# timer.net
KiCad netlist of a schematic drawn in EAGLE
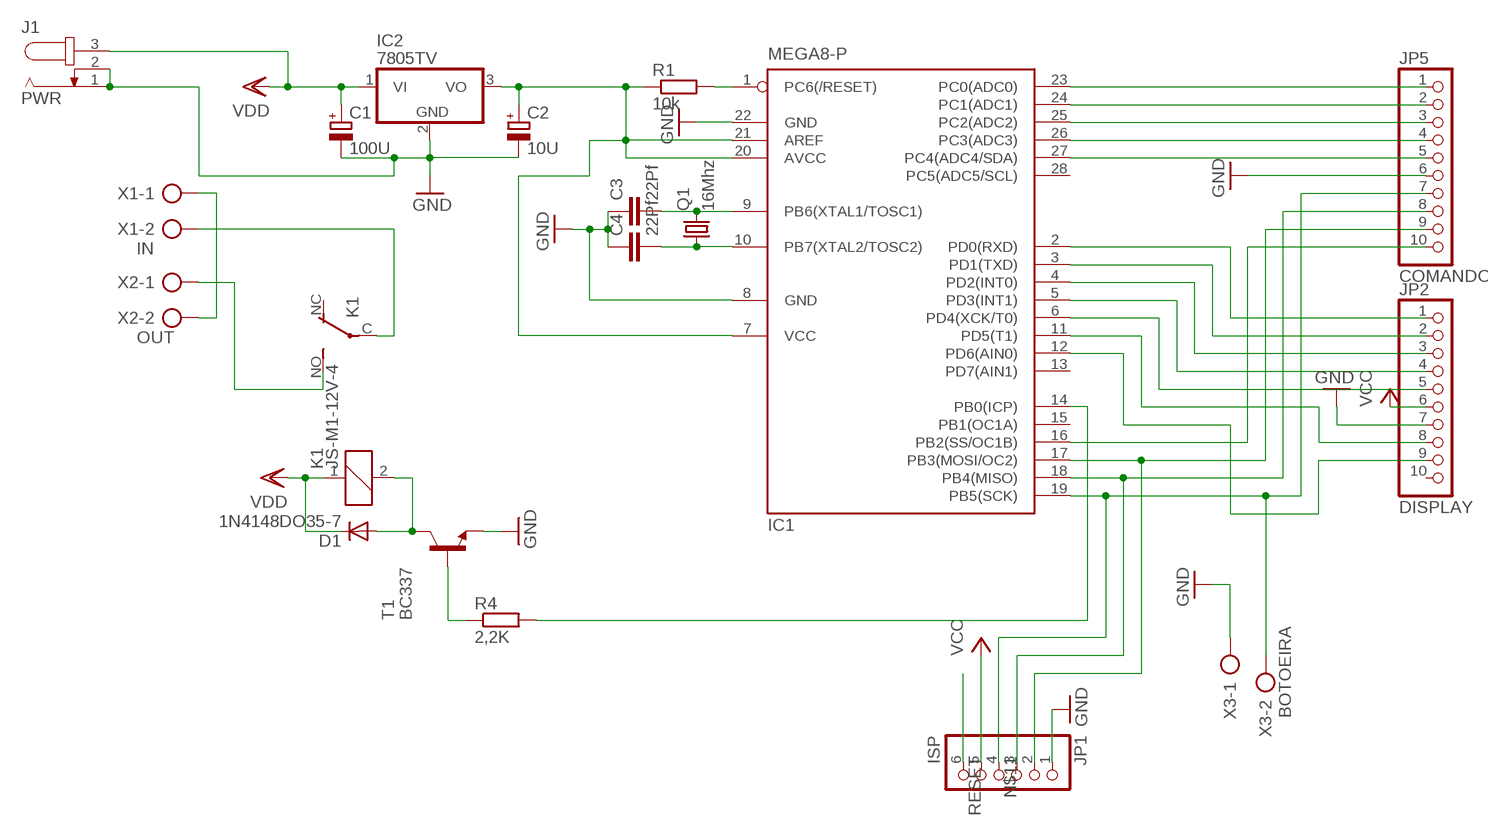
[diagram p0: schematic, sheet 1]

(export (version "E")
  (design (tool "Eeschema 10.0.6"))
  (components
    (comp (ref "C1")
      (value "100U")
      (footprint "eagle-import:E2,5-6")
      (libsource (lib "eagle-import") (part "CPOL-EUE2.5-6"))
    )
    (comp (ref "C2")
      (value "10U")
      (footprint "eagle-import:E2,5-6")
      (libsource (lib "eagle-import") (part "CPOL-EUE2.5-6"))
    )
    (comp (ref "C3")
      (value "22Pf")
      (footprint "eagle-import:C025-025X050")
      (libsource (lib "eagle-import") (part "C-EU025-025X050"))
    )
    (comp (ref "C4")
      (value "22Pf")
      (footprint "eagle-import:C025-025X050")
      (libsource (lib "eagle-import") (part "C-EU025-025X050"))
    )
    (comp (ref "D1")
      (value "1N4148DO35-7")
      (footprint "eagle-import:DO35-7")
      (libsource (lib "eagle-import") (part "1N4148DO35-7"))
    )
    (comp (ref "IC1")
      (value "MEGA8-P")
      (footprint "eagle-import:DIL28-3")
      (libsource (lib "eagle-import") (part "MEGA8-P"))
    )
    (comp (ref "IC2")
      (value "7805TV")
      (footprint "eagle-import:TO220V")
      (libsource (lib "eagle-import") (part "78TV05"))
    )
    (comp (ref "J1")
      (value "PWR")
      (footprint "eagle-import:SPC4078")
      (libsource (lib "eagle-import") (part "JACK-PLUG1"))
    )
    (comp (ref "JP1")
      (value "ISP")
      (footprint "eagle-import:1X06")
      (libsource (lib "eagle-import") (part "PINHD-1X6"))
    )
    (comp (ref "JP2")
      (value "DISPLAY")
      (footprint "eagle-import:1X10")
      (libsource (lib "eagle-import") (part "PINHD-1X10"))
    )
    (comp (ref "JP5")
      (value "COMANDO")
      (footprint "eagle-import:1X10")
      (libsource (lib "eagle-import") (part "PINHD-1X10"))
    )
    (comp (ref "K1")
      (value "JS-M1-12V-4")
      (footprint "eagle-import:JS-M")
      (fields (field (name "MPN") "JSM1-12V-4"))
      (libsource (lib "eagle-import") (part "JS-M1-12V-4"))
    )
    (comp (ref "Q1")
      (value "16Mhz")
      (footprint "eagle-import:HC49_S")
      (libsource (lib "eagle-import") (part "CRYSTALHC49S"))
    )
    (comp (ref "R1")
      (value "10k")
      (footprint "eagle-import:0204_7")
      (libsource (lib "eagle-import") (part "R-EU_0204/7"))
    )
    (comp (ref "R4")
      (value "2,2K")
      (footprint "eagle-import:0204_7")
      (libsource (lib "eagle-import") (part "R-EU_0204/7"))
    )
    (comp (ref "T1")
      (value "BC337")
      (footprint "eagle-import:TO92")
      (libsource (lib "eagle-import") (part "BC337"))
    )
    (comp (ref "X1")
      (value "IN")
      (footprint "eagle-import:AK500_2")
      (libsource (lib "eagle-import") (part "AK500/2"))
    )
    (comp (ref "X2")
      (value "OUT")
      (footprint "eagle-import:AK500_2")
      (libsource (lib "eagle-import") (part "AK500/2"))
    )
    (comp (ref "X3")
      (value "BOTOEIRA")
      (footprint "eagle-import:AK500_2")
      (libsource (lib "eagle-import") (part "AK500/2"))
    )
  )
  (nets
    (net (code "1") (name "/N$11") (class "Default")
      (node (ref "IC1") (pin "19") (pinfunction "PB5(SCK)_19") (pintype "bidirectional"))
      (node (ref "JP1") (pin "4") (pinfunction "4_4") (pintype "passive"))
      (node (ref "JP5") (pin "7") (pinfunction "7_7") (pintype "passive"))
      (node (ref "X3") (pin "2") (pinfunction "KL_2") (pintype "passive"))
    )
    (net (code "2") (name "/RESET") (class "Default")
      (node (ref "IC1") (pin "1") (pinfunction "PC6(/RESET)_1") (pintype "bidirectional"))
      (node (ref "JP1") (pin "6") (pinfunction "6_6") (pintype "passive"))
      (node (ref "R1") (pin "2") (pinfunction "2_2") (pintype "passive"))
    )
    (net (code "3") (name "GND") (class "Default")
      (node (ref "C1") (pin "-") (pinfunction "-_-") (pintype "passive"))
      (node (ref "C2") (pin "-") (pinfunction "-_-") (pintype "passive"))
      (node (ref "C3") (pin "1") (pinfunction "1_1") (pintype "passive"))
      (node (ref "C4") (pin "1") (pinfunction "1_1") (pintype "passive"))
      (node (ref "IC1") (pin "22") (pinfunction "GND_22") (pintype "power_in"))
      (node (ref "IC1") (pin "8") (pinfunction "GND_8") (pintype "power_in"))
      (node (ref "IC2") (pin "2") (pinfunction "GND_2") (pintype "passive"))
      (node (ref "J1") (pin "1") (pinfunction "1_1") (pintype "passive"))
      (node (ref "J1") (pin "2") (pinfunction "2_2") (pintype "passive"))
      (node (ref "JP1") (pin "1") (pinfunction "1_1") (pintype "passive"))
      (node (ref "JP2") (pin "7") (pinfunction "7_7") (pintype "passive"))
      (node (ref "JP5") (pin "6") (pinfunction "6_6") (pintype "passive"))
      (node (ref "T1") (pin "1") (pinfunction "E_1") (pintype "passive"))
      (node (ref "X3") (pin "1") (pinfunction "KL_1") (pintype "passive"))
    )
    (net (code "4") (name "Net-(IC1-PB0(ICP))") (class "Default")
      (node (ref "IC1") (pin "14") (pinfunction "PB0(ICP)_14") (pintype "bidirectional"))
      (node (ref "R4") (pin "2") (pinfunction "2_2") (pintype "passive"))
    )
    (net (code "5") (name "Net-(IC1-PB2(SS{slash}OC1B))") (class "Default")
      (node (ref "IC1") (pin "16") (pinfunction "PB2(SS/OC1B)_16") (pintype "bidirectional"))
      (node (ref "JP5") (pin "10") (pinfunction "10_10") (pintype "passive"))
    )
    (net (code "6") (name "Net-(IC1-PB3(MOSI{slash}OC2))") (class "Default")
      (node (ref "IC1") (pin "17") (pinfunction "PB3(MOSI/OC2)_17") (pintype "bidirectional"))
      (node (ref "JP1") (pin "2") (pinfunction "2_2") (pintype "passive"))
      (node (ref "JP5") (pin "9") (pinfunction "9_9") (pintype "passive"))
    )
    (net (code "7") (name "Net-(IC1-PB4(MISO))") (class "Default")
      (node (ref "IC1") (pin "18") (pinfunction "PB4(MISO)_18") (pintype "bidirectional"))
      (node (ref "JP1") (pin "3") (pinfunction "3_3") (pintype "passive"))
      (node (ref "JP5") (pin "8") (pinfunction "8_8") (pintype "passive"))
    )
    (net (code "8") (name "Net-(IC1-PB6(XTAL1{slash}TOSC1))") (class "Default")
      (node (ref "C3") (pin "2") (pinfunction "2_2") (pintype "passive"))
      (node (ref "IC1") (pin "9") (pinfunction "PB6(XTAL1/TOSC1)_9") (pintype "bidirectional"))
      (node (ref "Q1") (pin "2") (pinfunction "2_2") (pintype "passive"))
    )
    (net (code "9") (name "Net-(IC1-PB7(XTAL2{slash}TOSC2))") (class "Default")
      (node (ref "C4") (pin "2") (pinfunction "2_2") (pintype "passive"))
      (node (ref "IC1") (pin "10") (pinfunction "PB7(XTAL2/TOSC2)_10") (pintype "bidirectional"))
      (node (ref "Q1") (pin "1") (pinfunction "1_1") (pintype "passive"))
    )
    (net (code "10") (name "Net-(IC1-PC0(ADC0))") (class "Default")
      (node (ref "IC1") (pin "23") (pinfunction "PC0(ADC0)_23") (pintype "bidirectional"))
      (node (ref "JP5") (pin "1") (pinfunction "1_1") (pintype "passive"))
    )
    (net (code "11") (name "Net-(IC1-PC1(ADC1))") (class "Default")
      (node (ref "IC1") (pin "24") (pinfunction "PC1(ADC1)_24") (pintype "bidirectional"))
      (node (ref "JP5") (pin "2") (pinfunction "2_2") (pintype "passive"))
    )
    (net (code "12") (name "Net-(IC1-PC2(ADC2))") (class "Default")
      (node (ref "IC1") (pin "25") (pinfunction "PC2(ADC2)_25") (pintype "bidirectional"))
      (node (ref "JP5") (pin "3") (pinfunction "3_3") (pintype "passive"))
    )
    (net (code "13") (name "Net-(IC1-PC3(ADC3))") (class "Default")
      (node (ref "IC1") (pin "26") (pinfunction "PC3(ADC3)_26") (pintype "bidirectional"))
      (node (ref "JP5") (pin "4") (pinfunction "4_4") (pintype "passive"))
    )
    (net (code "14") (name "Net-(IC1-PC4(ADC4{slash}SDA))") (class "Default")
      (node (ref "IC1") (pin "27") (pinfunction "PC4(ADC4/SDA)_27") (pintype "bidirectional"))
      (node (ref "JP5") (pin "5") (pinfunction "5_5") (pintype "passive"))
    )
    (net (code "15") (name "Net-(IC1-PD0(RXD))") (class "Default")
      (node (ref "IC1") (pin "2") (pinfunction "PD0(RXD)_2") (pintype "bidirectional"))
      (node (ref "JP2") (pin "1") (pinfunction "1_1") (pintype "passive"))
    )
    (net (code "16") (name "Net-(IC1-PD1(TXD))") (class "Default")
      (node (ref "IC1") (pin "3") (pinfunction "PD1(TXD)_3") (pintype "bidirectional"))
      (node (ref "JP2") (pin "2") (pinfunction "2_2") (pintype "passive"))
    )
    (net (code "17") (name "Net-(IC1-PD2(INT0))") (class "Default")
      (node (ref "IC1") (pin "4") (pinfunction "PD2(INT0)_4") (pintype "bidirectional"))
      (node (ref "JP2") (pin "3") (pinfunction "3_3") (pintype "passive"))
    )
    (net (code "18") (name "Net-(IC1-PD3(INT1))") (class "Default")
      (node (ref "IC1") (pin "5") (pinfunction "PD3(INT1)_5") (pintype "bidirectional"))
      (node (ref "JP2") (pin "4") (pinfunction "4_4") (pintype "passive"))
    )
    (net (code "19") (name "Net-(IC1-PD4(XCK{slash}T0))") (class "Default")
      (node (ref "IC1") (pin "6") (pinfunction "PD4(XCK/T0)_6") (pintype "bidirectional"))
      (node (ref "JP2") (pin "5") (pinfunction "5_5") (pintype "passive"))
    )
    (net (code "20") (name "Net-(IC1-PD5(T1))") (class "Default")
      (node (ref "IC1") (pin "11") (pinfunction "PD5(T1)_11") (pintype "bidirectional"))
      (node (ref "JP2") (pin "8") (pinfunction "8_8") (pintype "passive"))
    )
    (net (code "21") (name "Net-(IC1-PD6(AIN0))") (class "Default")
      (node (ref "IC1") (pin "12") (pinfunction "PD6(AIN0)_12") (pintype "bidirectional"))
      (node (ref "JP2") (pin "9") (pinfunction "9_9") (pintype "passive"))
    )
    (net (code "22") (name "Net-(K1B-P)") (class "Default")
      (node (ref "K1") (pin "C") (pinfunction "P_C") (pintype "passive"))
      (node (ref "X1") (pin "2") (pinfunction "KL_2") (pintype "passive"))
    )
    (net (code "23") (name "Net-(K1B-S)") (class "Default")
      (node (ref "K1") (pin "NO") (pinfunction "S_NO") (pintype "passive"))
      (node (ref "X2") (pin "1") (pinfunction "KL_1") (pintype "passive"))
    )
    (net (code "24") (name "Net-(T1-B)") (class "Default")
      (node (ref "R4") (pin "1") (pinfunction "1_1") (pintype "passive"))
      (node (ref "T1") (pin "2") (pinfunction "B_2") (pintype "passive"))
    )
    (net (code "25") (name "Net-(T1-C)") (class "Default")
      (node (ref "D1") (pin "A") (pinfunction "A_A") (pintype "passive"))
      (node (ref "K1") (pin "2") (pinfunction "2_2") (pintype "passive"))
      (node (ref "T1") (pin "3") (pinfunction "C_3") (pintype "passive"))
    )
    (net (code "26") (name "Net-(X1A-KL)") (class "Default")
      (node (ref "X1") (pin "1") (pinfunction "KL_1") (pintype "passive"))
      (node (ref "X2") (pin "2") (pinfunction "KL_2") (pintype "passive"))
    )
    (net (code "27") (name "VCC") (class "Default")
      (node (ref "C2") (pin "+") (pinfunction "+_+") (pintype "passive"))
      (node (ref "IC1") (pin "20") (pinfunction "AVCC_20") (pintype "power_in"))
      (node (ref "IC1") (pin "21") (pinfunction "AREF_21") (pintype "passive"))
      (node (ref "IC1") (pin "7") (pinfunction "VCC_7") (pintype "power_in"))
      (node (ref "IC2") (pin "3") (pinfunction "VO_3") (pintype "passive"))
      (node (ref "JP1") (pin "5") (pinfunction "5_5") (pintype "passive"))
      (node (ref "JP2") (pin "6") (pinfunction "6_6") (pintype "passive"))
      (node (ref "R1") (pin "1") (pinfunction "1_1") (pintype "passive"))
    )
    (net (code "28") (name "VDD") (class "Default")
      (node (ref "C1") (pin "+") (pinfunction "+_+") (pintype "passive"))
      (node (ref "D1") (pin "C") (pinfunction "C_C") (pintype "passive"))
      (node (ref "IC2") (pin "1") (pinfunction "VI_1") (pintype "input"))
      (node (ref "J1") (pin "3") (pinfunction "3_3") (pintype "passive"))
      (node (ref "K1") (pin "1") (pinfunction "1_1") (pintype "passive"))
    )
    (net (code "29") (name "unconnected-(IC1-PB1(OC1A)-Pad15)") (class "Default")
      (node (ref "IC1") (pin "15") (pinfunction "PB1(OC1A)_15") (pintype "bidirectional"))
    )
    (net (code "30") (name "unconnected-(IC1-PC5(ADC5{slash}SCL)-Pad28)") (class "Default")
      (node (ref "IC1") (pin "28") (pinfunction "PC5(ADC5/SCL)_28") (pintype "bidirectional"))
    )
    (net (code "31") (name "unconnected-(IC1-PD7(AIN1)-Pad13)") (class "Default")
      (node (ref "IC1") (pin "13") (pinfunction "PD7(AIN1)_13") (pintype "bidirectional"))
    )
    (net (code "32") (name "unconnected-(JP2-Pad10)") (class "Default")
      (node (ref "JP2") (pin "10") (pinfunction "10_10") (pintype "passive"))
    )
    (net (code "33") (name "unconnected-(K1B-O-PadNC)") (class "Default")
      (node (ref "K1") (pin "NC") (pinfunction "O_NC") (pintype "passive"))
    )
  )
)
